# FinalSchematic1_1.net
KiCad netlist of a schematic drawn in EAGLE
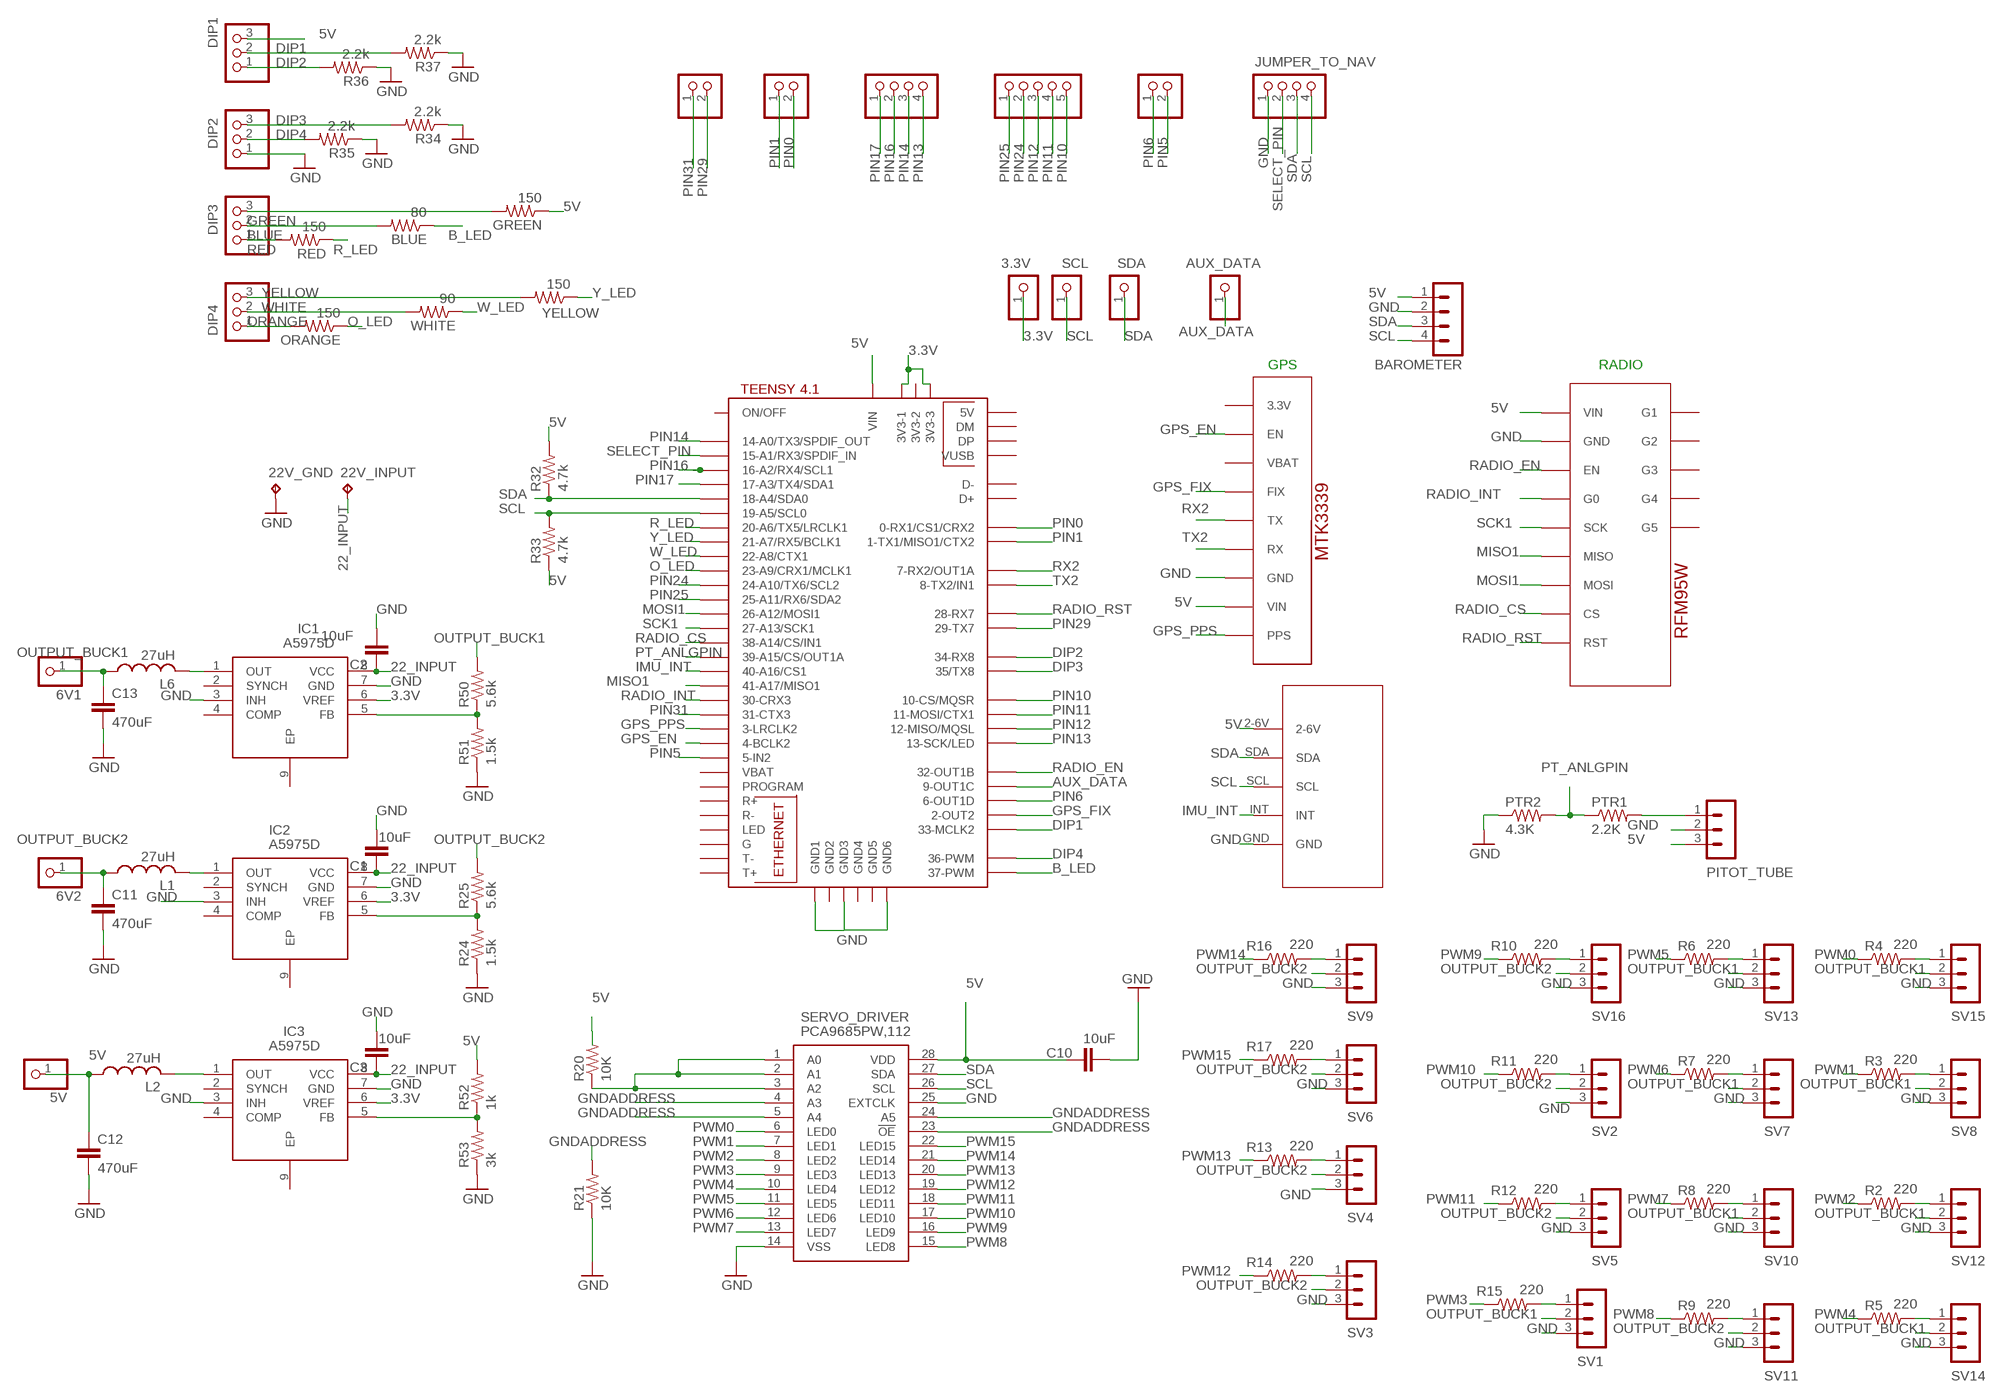
[diagram p0: schematic, sheet 1]

(export (version "E")
  (design (tool "Eeschema 10.0.6"))
  (components
    (comp (ref "1")
      (value "PINHD-1X2")
      (footprint "eagle-import:1X02")
      (libsource (lib "eagle-import") (part "PINHD-1X2"))
    )
    (comp (ref "2")
      (value "PINHD-1X2")
      (footprint "eagle-import:1X02")
      (libsource (lib "eagle-import") (part "PINHD-1X2"))
    )
    (comp (ref "3")
      (value "PINHD-1X4")
      (footprint "eagle-import:1X04")
      (libsource (lib "eagle-import") (part "PINHD-1X4"))
    )
    (comp (ref "3.3V")
      (value "PINHD-1X1")
      (footprint "eagle-import:1X01")
      (libsource (lib "eagle-import") (part "PINHD-1X1"))
    )
    (comp (ref "4")
      (value "PINHD-1X5")
      (footprint "eagle-import:1X05")
      (libsource (lib "eagle-import") (part "PINHD-1X5"))
    )
    (comp (ref "5")
      (value "PINHD-1X2")
      (footprint "eagle-import:1X02")
      (libsource (lib "eagle-import") (part "PINHD-1X2"))
    )
    (comp (ref "5V")
      (value "PINHD-1X1")
      (footprint "eagle-import:1X01")
      (libsource (lib "eagle-import") (part "PINHD-1X1"))
    )
    (comp (ref "6V1")
      (value "PINHD-1X1")
      (footprint "eagle-import:1X01")
      (libsource (lib "eagle-import") (part "PINHD-1X1"))
    )
    (comp (ref "6V2")
      (value "PINHD-1X1")
      (footprint "eagle-import:1X01")
      (libsource (lib "eagle-import") (part "PINHD-1X1"))
    )
    (comp (ref "22V_GND")
      (value "TPPAD1-17Y")
      (footprint "eagle-import:P1-17Y")
      (libsource (lib "eagle-import") (part "TPPAD1-17Y"))
    )
    (comp (ref "22V_INPUT")
      (value "TPPAD1-17Y")
      (footprint "eagle-import:P1-17Y")
      (libsource (lib "eagle-import") (part "TPPAD1-17Y"))
    )
    (comp (ref "AUX_DATA")
      (value "PINHD-1X1")
      (footprint "eagle-import:1X01")
      (libsource (lib "eagle-import") (part "PINHD-1X1"))
    )
    (comp (ref "BAROMETER")
      (value "MA04-1")
      (footprint "eagle-import:MA04-1")
      (libsource (lib "eagle-import") (part "MA04-1"))
    )
    (comp (ref "BLUE")
      (value "80")
      (footprint "eagle-import:0204_7")
      (libsource (lib "eagle-import") (part "R-US_0204/7"))
    )
    (comp (ref "C1")
      (value "10uF")
      (footprint "eagle-import:C2.5-3")
      (libsource (lib "eagle-import") (part "C2,5-3"))
    )
    (comp (ref "C2")
      (value "10uF")
      (footprint "eagle-import:C2.5-3")
      (libsource (lib "eagle-import") (part "C2,5-3"))
    )
    (comp (ref "C3")
      (value "10uF")
      (footprint "eagle-import:C2.5-3")
      (libsource (lib "eagle-import") (part "C2,5-3"))
    )
    (comp (ref "C10")
      (value "10uF")
      (footprint "eagle-import:C2.5-3")
      (libsource (lib "eagle-import") (part "C2,5-3"))
    )
    (comp (ref "C11")
      (value "470uF")
      (footprint "eagle-import:C2.5-3")
      (libsource (lib "eagle-import") (part "C2,5-3"))
    )
    (comp (ref "C12")
      (value "470uF")
      (footprint "eagle-import:C2.5-3")
      (libsource (lib "eagle-import") (part "C2,5-3"))
    )
    (comp (ref "C13")
      (value "470uF")
      (footprint "eagle-import:C2.5-3")
      (libsource (lib "eagle-import") (part "C2,5-3"))
    )
    (comp (ref "DIP1")
      (value "PINHD-1X3")
      (footprint "eagle-import:1X03")
      (libsource (lib "eagle-import") (part "PINHD-1X3"))
    )
    (comp (ref "DIP2")
      (value "PINHD-1X3")
      (footprint "eagle-import:1X03")
      (libsource (lib "eagle-import") (part "PINHD-1X3"))
    )
    (comp (ref "DIP3")
      (value "PINHD-1X3")
      (footprint "eagle-import:1X03")
      (libsource (lib "eagle-import") (part "PINHD-1X3"))
    )
    (comp (ref "DIP4")
      (value "PINHD-1X3")
      (footprint "eagle-import:1X03")
      (libsource (lib "eagle-import") (part "PINHD-1X3"))
    )
    (comp (ref "GPSMTK3339")
      (value "ADAFRUIT_MTK3339_GPS")
      (footprint "eagle-import:ADAFRUIT_MTK3339_GPS")
      (libsource (lib "eagle-import") (part "ADAFRUIT_MTK3339_GPS"))
    )
    (comp (ref "GREEN")
      (value "150")
      (footprint "eagle-import:0204_7")
      (libsource (lib "eagle-import") (part "R-US_0204/7"))
    )
    (comp (ref "IC1")
      (value "A5975D")
      (footprint "eagle-import:SOIC127P600X170-9N")
      (fields (field (name "MOUSER_PART_NUMBER") "511-A5975D"))
      (libsource (lib "eagle-import") (part "A5975D"))
    )
    (comp (ref "IC2")
      (value "A5975D")
      (footprint "eagle-import:SOIC127P600X170-9N")
      (fields (field (name "MOUSER_PART_NUMBER") "511-A5975D"))
      (libsource (lib "eagle-import") (part "A5975D"))
    )
    (comp (ref "IC3")
      (value "A5975D")
      (footprint "eagle-import:SOIC127P600X170-9N")
      (fields (field (name "MOUSER_PART_NUMBER") "511-A5975D"))
      (libsource (lib "eagle-import") (part "A5975D"))
    )
    (comp (ref "IMU")
      (value "ICM20948BREAKOUTDEVICE")
      (footprint "eagle-import:ICM20948BREAKOUT")
      (fields (field (name "SPICEPREFIX") "X"))
      (libsource (lib "eagle-import") (part "ICM20948BREAKOUTDEVICE"))
    )
    (comp (ref "JUMPER_TO_NAV")
      (value "PINHD-1X4")
      (footprint "eagle-import:1X04")
      (libsource (lib "eagle-import") (part "PINHD-1X4"))
    )
    (comp (ref "L1")
      (value "27uH")
      (footprint "eagle-import:TFI0307")
      (libsource (lib "eagle-import") (part "L-USTFI0307"))
    )
    (comp (ref "L2")
      (value "27uH")
      (footprint "eagle-import:TFI0307")
      (libsource (lib "eagle-import") (part "L-USTFI0307"))
    )
    (comp (ref "L6")
      (value "27uH")
      (footprint "eagle-import:TFI0307")
      (libsource (lib "eagle-import") (part "L-USTFI0307"))
    )
    (comp (ref "ORANGE")
      (value "150")
      (footprint "eagle-import:0204_7")
      (libsource (lib "eagle-import") (part "R-US_0204/7"))
    )
    (comp (ref "PITOT_TUBE")
      (value "MA03-1")
      (footprint "eagle-import:MA03-1")
      (libsource (lib "eagle-import") (part "MA03-1"))
    )
    (comp (ref "PTR1")
      (value "2.2K")
      (footprint "eagle-import:0204_7")
      (libsource (lib "eagle-import") (part "R-US_0204/7"))
    )
    (comp (ref "PTR2")
      (value "4.3K")
      (footprint "eagle-import:0204_7")
      (libsource (lib "eagle-import") (part "R-US_0204/7"))
    )
    (comp (ref "R2")
      (value "220")
      (footprint "eagle-import:0204_7")
      (libsource (lib "eagle-import") (part "R-US_0204/7"))
    )
    (comp (ref "R3")
      (value "220")
      (footprint "eagle-import:0204_7")
      (libsource (lib "eagle-import") (part "R-US_0204/7"))
    )
    (comp (ref "R4")
      (value "220")
      (footprint "eagle-import:0204_7")
      (libsource (lib "eagle-import") (part "R-US_0204/7"))
    )
    (comp (ref "R5")
      (value "220")
      (footprint "eagle-import:0204_7")
      (libsource (lib "eagle-import") (part "R-US_0204/7"))
    )
    (comp (ref "R6")
      (value "220")
      (footprint "eagle-import:0204_7")
      (libsource (lib "eagle-import") (part "R-US_0204/7"))
    )
    (comp (ref "R7")
      (value "220")
      (footprint "eagle-import:0204_7")
      (libsource (lib "eagle-import") (part "R-US_0204/7"))
    )
    (comp (ref "R8")
      (value "220")
      (footprint "eagle-import:0204_7")
      (libsource (lib "eagle-import") (part "R-US_0204/7"))
    )
    (comp (ref "R9")
      (value "220")
      (footprint "eagle-import:0204_7")
      (libsource (lib "eagle-import") (part "R-US_0204/7"))
    )
    (comp (ref "R10")
      (value "220")
      (footprint "eagle-import:0204_7")
      (libsource (lib "eagle-import") (part "R-US_0204/7"))
    )
    (comp (ref "R11")
      (value "220")
      (footprint "eagle-import:0204_7")
      (libsource (lib "eagle-import") (part "R-US_0204/7"))
    )
    (comp (ref "R12")
      (value "220")
      (footprint "eagle-import:0204_7")
      (libsource (lib "eagle-import") (part "R-US_0204/7"))
    )
    (comp (ref "R13")
      (value "220")
      (footprint "eagle-import:0204_7")
      (libsource (lib "eagle-import") (part "R-US_0204/7"))
    )
    (comp (ref "R14")
      (value "220")
      (footprint "eagle-import:0204_7")
      (libsource (lib "eagle-import") (part "R-US_0204/7"))
    )
    (comp (ref "R15")
      (value "220")
      (footprint "eagle-import:0204_7")
      (libsource (lib "eagle-import") (part "R-US_0204/7"))
    )
    (comp (ref "R16")
      (value "220")
      (footprint "eagle-import:0204_7")
      (libsource (lib "eagle-import") (part "R-US_0204/7"))
    )
    (comp (ref "R17")
      (value "220")
      (footprint "eagle-import:0204_7")
      (libsource (lib "eagle-import") (part "R-US_0204/7"))
    )
    (comp (ref "R20")
      (value "10K")
      (footprint "eagle-import:0204_7")
      (libsource (lib "eagle-import") (part "R-US_0204/7"))
    )
    (comp (ref "R21")
      (value "10K")
      (footprint "eagle-import:0204_7")
      (libsource (lib "eagle-import") (part "R-US_0204/7"))
    )
    (comp (ref "R24")
      (value "1.5k")
      (footprint "eagle-import:0204_7")
      (libsource (lib "eagle-import") (part "R-US_0204/7"))
    )
    (comp (ref "R25")
      (value "5.6k")
      (footprint "eagle-import:0204_7")
      (libsource (lib "eagle-import") (part "R-US_0204/7"))
    )
    (comp (ref "R32")
      (value "4.7k")
      (footprint "eagle-import:0204_7")
      (libsource (lib "eagle-import") (part "R-US_0204/7"))
    )
    (comp (ref "R33")
      (value "4.7k")
      (footprint "eagle-import:0204_7")
      (libsource (lib "eagle-import") (part "R-US_0204/7"))
    )
    (comp (ref "R34")
      (value "2.2k")
      (footprint "eagle-import:0204_7")
      (libsource (lib "eagle-import") (part "R-US_0204/7"))
    )
    (comp (ref "R35")
      (value "2.2k")
      (footprint "eagle-import:0204_7")
      (libsource (lib "eagle-import") (part "R-US_0204/7"))
    )
    (comp (ref "R36")
      (value "2.2k")
      (footprint "eagle-import:0204_7")
      (libsource (lib "eagle-import") (part "R-US_0204/7"))
    )
    (comp (ref "R37")
      (value "2.2k")
      (footprint "eagle-import:0204_7")
      (libsource (lib "eagle-import") (part "R-US_0204/7"))
    )
    (comp (ref "R50")
      (value "5.6k")
      (footprint "eagle-import:0204_7")
      (libsource (lib "eagle-import") (part "R-US_0204/7"))
    )
    (comp (ref "R51")
      (value "1.5k")
      (footprint "eagle-import:0204_7")
      (libsource (lib "eagle-import") (part "R-US_0204/7"))
    )
    (comp (ref "R52")
      (value "1k")
      (footprint "eagle-import:0204_7")
      (libsource (lib "eagle-import") (part "R-US_0204/7"))
    )
    (comp (ref "R53")
      (value "3k")
      (footprint "eagle-import:0204_7")
      (libsource (lib "eagle-import") (part "R-US_0204/7"))
    )
    (comp (ref "RADIO")
      (value "ADAFRUIT_RFM95W_LORA_RADIO")
      (footprint "eagle-import:ADAFRUIT_RFM95W_LORA_RADIO")
      (libsource (lib "eagle-import") (part "ADAFRUIT_RFM95W_LORA_RADIO"))
    )
    (comp (ref "RED")
      (value "150")
      (footprint "eagle-import:0204_7")
      (libsource (lib "eagle-import") (part "R-US_0204/7"))
    )
    (comp (ref "SCL")
      (value "PINHD-1X1")
      (footprint "eagle-import:1X01")
      (libsource (lib "eagle-import") (part "PINHD-1X1"))
    )
    (comp (ref "SDA")
      (value "PINHD-1X1")
      (footprint "eagle-import:1X01")
      (libsource (lib "eagle-import") (part "PINHD-1X1"))
    )
    (comp (ref "SERVO_DRIVER")
      (value "PCA9685PW,112")
      (footprint "eagle-import:SOP65P640X110-28N")
      (fields (field (name "MOUSER_PART_NUMBER") "771-PCA9685PW,112"))
      (libsource (lib "eagle-import") (part "PCA9685PW,112"))
    )
    (comp (ref "SV1")
      (value "MA03-1")
      (footprint "eagle-import:MA03-1")
      (libsource (lib "eagle-import") (part "MA03-1"))
    )
    (comp (ref "SV2")
      (value "MA03-1")
      (footprint "eagle-import:MA03-1")
      (libsource (lib "eagle-import") (part "MA03-1"))
    )
    (comp (ref "SV3")
      (value "MA03-1")
      (footprint "eagle-import:MA03-1")
      (libsource (lib "eagle-import") (part "MA03-1"))
    )
    (comp (ref "SV4")
      (value "MA03-1")
      (footprint "eagle-import:MA03-1")
      (libsource (lib "eagle-import") (part "MA03-1"))
    )
    (comp (ref "SV5")
      (value "MA03-1")
      (footprint "eagle-import:MA03-1")
      (libsource (lib "eagle-import") (part "MA03-1"))
    )
    (comp (ref "SV6")
      (value "MA03-1")
      (footprint "eagle-import:MA03-1")
      (libsource (lib "eagle-import") (part "MA03-1"))
    )
    (comp (ref "SV7")
      (value "MA03-1")
      (footprint "eagle-import:MA03-1")
      (libsource (lib "eagle-import") (part "MA03-1"))
    )
    (comp (ref "SV8")
      (value "MA03-1")
      (footprint "eagle-import:MA03-1")
      (libsource (lib "eagle-import") (part "MA03-1"))
    )
    (comp (ref "SV9")
      (value "MA03-1")
      (footprint "eagle-import:MA03-1")
      (libsource (lib "eagle-import") (part "MA03-1"))
    )
    (comp (ref "SV10")
      (value "MA03-1")
      (footprint "eagle-import:MA03-1")
      (libsource (lib "eagle-import") (part "MA03-1"))
    )
    (comp (ref "SV11")
      (value "MA03-1")
      (footprint "eagle-import:MA03-1")
      (libsource (lib "eagle-import") (part "MA03-1"))
    )
    (comp (ref "SV12")
      (value "MA03-1")
      (footprint "eagle-import:MA03-1")
      (libsource (lib "eagle-import") (part "MA03-1"))
    )
    (comp (ref "SV13")
      (value "MA03-1")
      (footprint "eagle-import:MA03-1")
      (libsource (lib "eagle-import") (part "MA03-1"))
    )
    (comp (ref "SV14")
      (value "MA03-1")
      (footprint "eagle-import:MA03-1")
      (libsource (lib "eagle-import") (part "MA03-1"))
    )
    (comp (ref "SV15")
      (value "MA03-1")
      (footprint "eagle-import:MA03-1")
      (libsource (lib "eagle-import") (part "MA03-1"))
    )
    (comp (ref "SV16")
      (value "MA03-1")
      (footprint "eagle-import:MA03-1")
      (libsource (lib "eagle-import") (part "MA03-1"))
    )
    (comp (ref "TEENSY4.1")
      (value "TEENSY41")
      (footprint "eagle-import:TEENSY41")
      (libsource (lib "eagle-import") (part "TEENSY41"))
    )
    (comp (ref "WHITE")
      (value "90")
      (footprint "eagle-import:0204_7")
      (libsource (lib "eagle-import") (part "R-US_0204/7"))
    )
    (comp (ref "YELLOW")
      (value "150")
      (footprint "eagle-import:0204_7")
      (libsource (lib "eagle-import") (part "R-US_0204/7"))
    )
  )
  (nets
    (net (code "1") (name "/3.3V") (class "Default")
      (node (ref "3.3V") (pin "1") (pinfunction "1_1") (pintype "passive"))
      (node (ref "IC1") (pin "6") (pinfunction "VREF_6") (pintype "bidirectional"))
      (node (ref "IC2") (pin "6") (pinfunction "VREF_6") (pintype "bidirectional"))
      (node (ref "IC3") (pin "6") (pinfunction "VREF_6") (pintype "bidirectional"))
      (node (ref "TEENSY4.1") (pin "3V3-1") (pinfunction "3V3-1_3V3-1") (pintype "bidirectional"))
      (node (ref "TEENSY4.1") (pin "3V3-3") (pinfunction "3V3-3_3V3-3") (pintype "bidirectional"))
    )
    (net (code "2") (name "/5V") (class "Default")
      (node (ref "5V") (pin "1") (pinfunction "1_1") (pintype "passive"))
      (node (ref "BAROMETER") (pin "1") (pinfunction "1_1") (pintype "passive"))
      (node (ref "C10") (pin "1") (pinfunction "1_1") (pintype "passive"))
      (node (ref "C12") (pin "1") (pinfunction "1_1") (pintype "passive"))
      (node (ref "DIP1") (pin "3") (pinfunction "3_3") (pintype "passive"))
      (node (ref "GPSMTK3339") (pin "VIN") (pinfunction "VIN_VIN") (pintype "bidirectional"))
      (node (ref "GREEN") (pin "1") (pinfunction "1_1") (pintype "passive"))
      (node (ref "IMU") (pin "2-6V") (pinfunction "2-6V_2-6V") (pintype "bidirectional"))
      (node (ref "L2") (pin "1") (pinfunction "1_1") (pintype "passive"))
      (node (ref "PITOT_TUBE") (pin "3") (pinfunction "3_3") (pintype "passive"))
      (node (ref "R20") (pin "2") (pinfunction "2_2") (pintype "passive"))
      (node (ref "R32") (pin "2") (pinfunction "2_2") (pintype "passive"))
      (node (ref "R33") (pin "1") (pinfunction "1_1") (pintype "passive"))
      (node (ref "R52") (pin "2") (pinfunction "2_2") (pintype "passive"))
      (node (ref "RADIO") (pin "1") (pinfunction "VIN_1") (pintype "bidirectional"))
      (node (ref "SERVO_DRIVER") (pin "28") (pinfunction "VDD_28") (pintype "bidirectional"))
      (node (ref "TEENSY4.1") (pin "VIN") (pinfunction "VIN_VIN") (pintype "bidirectional"))
    )
    (net (code "3") (name "/22_INPUT") (class "Default")
      (node (ref "22V_INPUT") (pin "TP") (pinfunction "TP_TP") (pintype "input"))
      (node (ref "C1") (pin "1") (pinfunction "1_1") (pintype "passive"))
      (node (ref "C2") (pin "1") (pinfunction "1_1") (pintype "passive"))
      (node (ref "C3") (pin "1") (pinfunction "1_1") (pintype "passive"))
      (node (ref "IC1") (pin "8") (pinfunction "VCC_8") (pintype "bidirectional"))
      (node (ref "IC2") (pin "8") (pinfunction "VCC_8") (pintype "bidirectional"))
      (node (ref "IC3") (pin "8") (pinfunction "VCC_8") (pintype "bidirectional"))
    )
    (net (code "4") (name "/AUX_DATA") (class "Default")
      (node (ref "AUX_DATA") (pin "1") (pinfunction "1_1") (pintype "passive"))
      (node (ref "TEENSY4.1") (pin "9-OUT1C") (pinfunction "9-OUT1C_9-OUT1C") (pintype "bidirectional"))
    )
    (net (code "5") (name "/BLUE") (class "Default")
      (node (ref "BLUE") (pin "2") (pinfunction "2_2") (pintype "passive"))
      (node (ref "DIP3") (pin "2") (pinfunction "2_2") (pintype "passive"))
    )
    (net (code "6") (name "/B_LED") (class "Default")
      (node (ref "BLUE") (pin "1") (pinfunction "1_1") (pintype "passive"))
      (node (ref "TEENSY4.1") (pin "37-PWM") (pinfunction "37-PWM_37-PWM") (pintype "bidirectional"))
    )
    (net (code "7") (name "/DIP1") (class "Default")
      (node (ref "DIP1") (pin "2") (pinfunction "2_2") (pintype "passive"))
      (node (ref "R37") (pin "2") (pinfunction "2_2") (pintype "passive"))
      (node (ref "TEENSY4.1") (pin "33-MCLK2") (pinfunction "33-MCLK2_33-MCLK2") (pintype "bidirectional"))
    )
    (net (code "8") (name "/DIP2") (class "Default")
      (node (ref "DIP1") (pin "1") (pinfunction "1_1") (pintype "passive"))
      (node (ref "R36") (pin "2") (pinfunction "2_2") (pintype "passive"))
      (node (ref "TEENSY4.1") (pin "34-RX8") (pinfunction "34-RX8_34-RX8") (pintype "bidirectional"))
    )
    (net (code "9") (name "/DIP3") (class "Default")
      (node (ref "DIP2") (pin "3") (pinfunction "3_3") (pintype "passive"))
      (node (ref "R34") (pin "2") (pinfunction "2_2") (pintype "passive"))
      (node (ref "TEENSY4.1") (pin "35-TX8") (pinfunction "35/TX8_35-TX8") (pintype "bidirectional"))
    )
    (net (code "10") (name "/DIP4") (class "Default")
      (node (ref "DIP2") (pin "2") (pinfunction "2_2") (pintype "passive"))
      (node (ref "R35") (pin "2") (pinfunction "2_2") (pintype "passive"))
      (node (ref "TEENSY4.1") (pin "36-PWM") (pinfunction "36-PWM_36-PWM") (pintype "bidirectional"))
    )
    (net (code "11") (name "/GNDADDRESS") (class "Default")
      (node (ref "R21") (pin "2") (pinfunction "2_2") (pintype "passive"))
      (node (ref "SERVO_DRIVER") (pin "23") (pinfunction "~{OE}_23") (pintype "bidirectional"))
      (node (ref "SERVO_DRIVER") (pin "24") (pinfunction "A5_24") (pintype "bidirectional"))
      (node (ref "SERVO_DRIVER") (pin "4") (pinfunction "A3_4") (pintype "bidirectional"))
      (node (ref "SERVO_DRIVER") (pin "5") (pinfunction "A4_5") (pintype "bidirectional"))
    )
    (net (code "12") (name "/GPS_EN") (class "Default")
      (node (ref "GPSMTK3339") (pin "EN") (pinfunction "EN_EN") (pintype "bidirectional"))
      (node (ref "TEENSY4.1") (pin "4-BCLK2") (pinfunction "4-BCLK2_4-BCLK2") (pintype "bidirectional"))
    )
    (net (code "13") (name "/GPS_FIX") (class "Default")
      (node (ref "GPSMTK3339") (pin "FIX") (pinfunction "FIX_FIX") (pintype "bidirectional"))
      (node (ref "TEENSY4.1") (pin "2-OUT2") (pinfunction "2-OUT2_2-OUT2") (pintype "bidirectional"))
    )
    (net (code "14") (name "/GPS_PPS") (class "Default")
      (node (ref "GPSMTK3339") (pin "PPS") (pinfunction "PPS_PPS") (pintype "bidirectional"))
      (node (ref "TEENSY4.1") (pin "3-LRCLK2") (pinfunction "3-LRCLK2_3-LRCLK2") (pintype "bidirectional"))
    )
    (net (code "15") (name "/GREEN") (class "Default")
      (node (ref "DIP3") (pin "3") (pinfunction "3_3") (pintype "passive"))
      (node (ref "GREEN") (pin "2") (pinfunction "2_2") (pintype "passive"))
    )
    (net (code "16") (name "/IMU_INT") (class "Default")
      (node (ref "IMU") (pin "INT") (pinfunction "INT_INT") (pintype "bidirectional"))
      (node (ref "TEENSY4.1") (pin "40-A16/CS1") (pinfunction "40-A16/CS1_40-A16/CS1") (pintype "bidirectional"))
    )
    (net (code "17") (name "/MISO1") (class "Default")
      (node (ref "RADIO") (pin "6") (pinfunction "MISO_6") (pintype "bidirectional"))
      (node (ref "TEENSY4.1") (pin "41-A17/MISO1") (pinfunction "41-A17/MISO1_41-A17/MISO1") (pintype "bidirectional"))
    )
    (net (code "18") (name "/MOSI1") (class "Default")
      (node (ref "RADIO") (pin "7") (pinfunction "MOSI_7") (pintype "bidirectional"))
      (node (ref "TEENSY4.1") (pin "26-A12/MOSI1") (pinfunction "26-A12/MOSI1_26-A12/MOSI1") (pintype "bidirectional"))
    )
    (net (code "19") (name "/ORANGE") (class "Default")
      (node (ref "DIP4") (pin "1") (pinfunction "1_1") (pintype "passive"))
      (node (ref "ORANGE") (pin "2") (pinfunction "2_2") (pintype "passive"))
    )
    (net (code "20") (name "/OUTPUT_BUCK1") (class "Default")
      (node (ref "6V1") (pin "1") (pinfunction "1_1") (pintype "passive"))
      (node (ref "C13") (pin "1") (pinfunction "1_1") (pintype "passive"))
      (node (ref "L6") (pin "1") (pinfunction "1_1") (pintype "passive"))
      (node (ref "R50") (pin "2") (pinfunction "2_2") (pintype "passive"))
      (node (ref "SV1") (pin "2") (pinfunction "2_2") (pintype "passive"))
      (node (ref "SV10") (pin "2") (pinfunction "2_2") (pintype "passive"))
      (node (ref "SV12") (pin "2") (pinfunction "2_2") (pintype "passive"))
      (node (ref "SV13") (pin "2") (pinfunction "2_2") (pintype "passive"))
      (node (ref "SV14") (pin "2") (pinfunction "2_2") (pintype "passive"))
      (node (ref "SV15") (pin "2") (pinfunction "2_2") (pintype "passive"))
      (node (ref "SV7") (pin "2") (pinfunction "2_2") (pintype "passive"))
      (node (ref "SV8") (pin "2") (pinfunction "2_2") (pintype "passive"))
    )
    (net (code "21") (name "/OUTPUT_BUCK2") (class "Default")
      (node (ref "6V2") (pin "1") (pinfunction "1_1") (pintype "passive"))
      (node (ref "C11") (pin "1") (pinfunction "1_1") (pintype "passive"))
      (node (ref "L1") (pin "1") (pinfunction "1_1") (pintype "passive"))
      (node (ref "R25") (pin "2") (pinfunction "2_2") (pintype "passive"))
      (node (ref "SV11") (pin "2") (pinfunction "2_2") (pintype "passive"))
      (node (ref "SV16") (pin "2") (pinfunction "2_2") (pintype "passive"))
      (node (ref "SV2") (pin "2") (pinfunction "2_2") (pintype "passive"))
      (node (ref "SV3") (pin "2") (pinfunction "2_2") (pintype "passive"))
      (node (ref "SV4") (pin "2") (pinfunction "2_2") (pintype "passive"))
      (node (ref "SV5") (pin "2") (pinfunction "2_2") (pintype "passive"))
      (node (ref "SV6") (pin "2") (pinfunction "2_2") (pintype "passive"))
      (node (ref "SV9") (pin "2") (pinfunction "2_2") (pintype "passive"))
    )
    (net (code "22") (name "/O_LED") (class "Default")
      (node (ref "ORANGE") (pin "1") (pinfunction "1_1") (pintype "passive"))
      (node (ref "TEENSY4.1") (pin "23-A9/CRX1/MCLK1") (pinfunction "23-A9/CRX1/MCLK1_23-A9/CRX1/MCLK1") (pintype "bidirectional"))
    )
    (net (code "23") (name "/PIN0") (class "Default")
      (node (ref "2") (pin "2") (pinfunction "2_2") (pintype "passive"))
      (node (ref "TEENSY4.1") (pin "0-RX1/CS1/CRX2") (pinfunction "0-RX1/CS1/CRX2_0-RX1/CS1/CRX2") (pintype "bidirectional"))
    )
    (net (code "24") (name "/PIN1") (class "Default")
      (node (ref "2") (pin "1") (pinfunction "1_1") (pintype "passive"))
      (node (ref "TEENSY4.1") (pin "1-TX1/MISO1/CTX2") (pinfunction "1-TX1/MISO1/CTX2_1-TX1/MISO1/CTX2") (pintype "bidirectional"))
    )
    (net (code "25") (name "/PIN5") (class "Default")
      (node (ref "5") (pin "2") (pinfunction "2_2") (pintype "passive"))
      (node (ref "TEENSY4.1") (pin "5-IN2") (pinfunction "5-IN2_5-IN2") (pintype "bidirectional"))
    )
    (net (code "26") (name "/PIN6") (class "Default")
      (node (ref "5") (pin "1") (pinfunction "1_1") (pintype "passive"))
      (node (ref "TEENSY4.1") (pin "6-OUT1D") (pinfunction "6-OUT1D_6-OUT1D") (pintype "bidirectional"))
    )
    (net (code "27") (name "/PIN10") (class "Default")
      (node (ref "4") (pin "5") (pinfunction "5_5") (pintype "passive"))
      (node (ref "TEENSY4.1") (pin "10-CS\\MQSR") (pinfunction "10-CS/MQSR_10-CS\\MQSR") (pintype "bidirectional"))
    )
    (net (code "28") (name "/PIN11") (class "Default")
      (node (ref "4") (pin "4") (pinfunction "4_4") (pintype "passive"))
      (node (ref "TEENSY4.1") (pin "11-MOSI/CTX1") (pinfunction "11-MOSI/CTX1_11-MOSI/CTX1") (pintype "bidirectional"))
    )
    (net (code "29") (name "/PIN12") (class "Default")
      (node (ref "4") (pin "3") (pinfunction "3_3") (pintype "passive"))
      (node (ref "TEENSY4.1") (pin "12-MISO/MQSL") (pinfunction "12-MISO/MQSL_12-MISO/MQSL") (pintype "bidirectional"))
    )
    (net (code "30") (name "/PIN13") (class "Default")
      (node (ref "3") (pin "4") (pinfunction "4_4") (pintype "passive"))
      (node (ref "TEENSY4.1") (pin "13-SCK/LED") (pinfunction "13-SCK/LED_13-SCK/LED") (pintype "bidirectional"))
    )
    (net (code "31") (name "/PIN14") (class "Default")
      (node (ref "3") (pin "3") (pinfunction "3_3") (pintype "passive"))
      (node (ref "TEENSY4.1") (pin "14-A0/TX3/SPDIF_OUT") (pinfunction "14-A0/TX3/SPDIF_OUT_14-A0/TX3/SPDIF_OUT") (pintype "bidirectional"))
    )
    (net (code "32") (name "/PIN16") (class "Default")
      (node (ref "3") (pin "2") (pinfunction "2_2") (pintype "passive"))
      (node (ref "TEENSY4.1") (pin "16-A2/RX4/SCL1") (pinfunction "16-A2/RX4/SCL1_16-A2/RX4/SCL1") (pintype "bidirectional"))
    )
    (net (code "33") (name "/PIN17") (class "Default")
      (node (ref "3") (pin "1") (pinfunction "1_1") (pintype "passive"))
      (node (ref "TEENSY4.1") (pin "17-A3/TX4/SDA1") (pinfunction "17-A3/TX4/SDA1_17-A3/TX4/SDA1") (pintype "bidirectional"))
    )
    (net (code "34") (name "/PIN24") (class "Default")
      (node (ref "4") (pin "2") (pinfunction "2_2") (pintype "passive"))
      (node (ref "TEENSY4.1") (pin "24-A10/TX6/SCL2") (pinfunction "24-A10/TX6/SCL2_24-A10/TX6/SCL2") (pintype "bidirectional"))
    )
    (net (code "35") (name "/PIN25") (class "Default")
      (node (ref "4") (pin "1") (pinfunction "1_1") (pintype "passive"))
      (node (ref "TEENSY4.1") (pin "25-A11/RX6/SDA2") (pinfunction "25-A11/RX6/SDA2_25-A11/RX6/SDA2") (pintype "bidirectional"))
    )
    (net (code "36") (name "/PIN29") (class "Default")
      (node (ref "1") (pin "2") (pinfunction "2_2") (pintype "passive"))
      (node (ref "TEENSY4.1") (pin "29-TX7") (pinfunction "29-TX7_29-TX7") (pintype "bidirectional"))
    )
    (net (code "37") (name "/PIN31") (class "Default")
      (node (ref "1") (pin "1") (pinfunction "1_1") (pintype "passive"))
      (node (ref "TEENSY4.1") (pin "31-CTX3") (pinfunction "31-CTX3_31-CTX3") (pintype "bidirectional"))
    )
    (net (code "38") (name "/PT_ANLGPIN") (class "Default")
      (node (ref "PTR1") (pin "1") (pinfunction "1_1") (pintype "passive"))
      (node (ref "PTR2") (pin "2") (pinfunction "2_2") (pintype "passive"))
      (node (ref "TEENSY4.1") (pin "39-A15/CS/OUT1A") (pinfunction "39-A15/CS/OUT1A_39-A15/CS/OUT1A") (pintype "bidirectional"))
    )
    (net (code "39") (name "/PWM0") (class "Default")
      (node (ref "R4") (pin "1") (pinfunction "1_1") (pintype "passive"))
      (node (ref "SERVO_DRIVER") (pin "6") (pinfunction "LED0_6") (pintype "bidirectional"))
    )
    (net (code "40") (name "/PWM1") (class "Default")
      (node (ref "R3") (pin "1") (pinfunction "1_1") (pintype "passive"))
      (node (ref "SERVO_DRIVER") (pin "7") (pinfunction "LED1_7") (pintype "bidirectional"))
    )
    (net (code "41") (name "/PWM2") (class "Default")
      (node (ref "R2") (pin "1") (pinfunction "1_1") (pintype "passive"))
      (node (ref "SERVO_DRIVER") (pin "8") (pinfunction "LED2_8") (pintype "bidirectional"))
    )
    (net (code "42") (name "/PWM3") (class "Default")
      (node (ref "R15") (pin "1") (pinfunction "1_1") (pintype "passive"))
      (node (ref "SERVO_DRIVER") (pin "9") (pinfunction "LED3_9") (pintype "bidirectional"))
    )
    (net (code "43") (name "/PWM4") (class "Default")
      (node (ref "R5") (pin "1") (pinfunction "1_1") (pintype "passive"))
      (node (ref "SERVO_DRIVER") (pin "10") (pinfunction "LED4_10") (pintype "bidirectional"))
    )
    (net (code "44") (name "/PWM5") (class "Default")
      (node (ref "R6") (pin "1") (pinfunction "1_1") (pintype "passive"))
      (node (ref "SERVO_DRIVER") (pin "11") (pinfunction "LED5_11") (pintype "bidirectional"))
    )
    (net (code "45") (name "/PWM6") (class "Default")
      (node (ref "R7") (pin "1") (pinfunction "1_1") (pintype "passive"))
      (node (ref "SERVO_DRIVER") (pin "12") (pinfunction "LED6_12") (pintype "bidirectional"))
    )
    (net (code "46") (name "/PWM7") (class "Default")
      (node (ref "R8") (pin "1") (pinfunction "1_1") (pintype "passive"))
      (node (ref "SERVO_DRIVER") (pin "13") (pinfunction "LED7_13") (pintype "bidirectional"))
    )
    (net (code "47") (name "/PWM8") (class "Default")
      (node (ref "R9") (pin "1") (pinfunction "1_1") (pintype "passive"))
      (node (ref "SERVO_DRIVER") (pin "15") (pinfunction "LED8_15") (pintype "bidirectional"))
    )
    (net (code "48") (name "/PWM9") (class "Default")
      (node (ref "R10") (pin "1") (pinfunction "1_1") (pintype "passive"))
      (node (ref "SERVO_DRIVER") (pin "16") (pinfunction "LED9_16") (pintype "bidirectional"))
    )
    (net (code "49") (name "/PWM10") (class "Default")
      (node (ref "R11") (pin "1") (pinfunction "1_1") (pintype "passive"))
      (node (ref "SERVO_DRIVER") (pin "17") (pinfunction "LED10_17") (pintype "bidirectional"))
    )
    (net (code "50") (name "/PWM11") (class "Default")
      (node (ref "R12") (pin "1") (pinfunction "1_1") (pintype "passive"))
      (node (ref "SERVO_DRIVER") (pin "18") (pinfunction "LED11_18") (pintype "bidirectional"))
    )
    (net (code "51") (name "/PWM12") (class "Default")
      (node (ref "R14") (pin "1") (pinfunction "1_1") (pintype "passive"))
      (node (ref "SERVO_DRIVER") (pin "19") (pinfunction "LED12_19") (pintype "bidirectional"))
    )
    (net (code "52") (name "/PWM13") (class "Default")
      (node (ref "R13") (pin "1") (pinfunction "1_1") (pintype "passive"))
      (node (ref "SERVO_DRIVER") (pin "20") (pinfunction "LED13_20") (pintype "bidirectional"))
    )
    (net (code "53") (name "/PWM14") (class "Default")
      (node (ref "R16") (pin "1") (pinfunction "1_1") (pintype "passive"))
      (node (ref "SERVO_DRIVER") (pin "21") (pinfunction "LED14_21") (pintype "bidirectional"))
    )
    (net (code "54") (name "/PWM15") (class "Default")
      (node (ref "R17") (pin "1") (pinfunction "1_1") (pintype "passive"))
      (node (ref "SERVO_DRIVER") (pin "22") (pinfunction "LED15_22") (pintype "bidirectional"))
    )
    (net (code "55") (name "/RADIO_CS") (class "Default")
      (node (ref "RADIO") (pin "8") (pinfunction "CS_8") (pintype "bidirectional"))
      (node (ref "TEENSY4.1") (pin "38-A14/CS/IN1") (pinfunction "38-A14/CS/IN1_38-A14/CS/IN1") (pintype "bidirectional"))
    )
    (net (code "56") (name "/RADIO_EN") (class "Default")
      (node (ref "RADIO") (pin "3") (pinfunction "EN_3") (pintype "bidirectional"))
      (node (ref "TEENSY4.1") (pin "32-OUT1B") (pinfunction "32-OUT1B_32-OUT1B") (pintype "bidirectional"))
    )
    (net (code "57") (name "/RADIO_INT") (class "Default")
      (node (ref "RADIO") (pin "4") (pinfunction "G0_4") (pintype "bidirectional"))
      (node (ref "TEENSY4.1") (pin "30-CRX3") (pinfunction "30-CRX3_30-CRX3") (pintype "bidirectional"))
    )
    (net (code "58") (name "/RADIO_RST") (class "Default")
      (node (ref "RADIO") (pin "9") (pinfunction "RST_9") (pintype "bidirectional"))
      (node (ref "TEENSY4.1") (pin "28-RX7") (pinfunction "28-RX7_28-RX7") (pintype "bidirectional"))
    )
    (net (code "59") (name "/RED") (class "Default")
      (node (ref "DIP3") (pin "1") (pinfunction "1_1") (pintype "passive"))
      (node (ref "RED") (pin "2") (pinfunction "2_2") (pintype "passive"))
    )
    (net (code "60") (name "/RX2") (class "Default")
      (node (ref "GPSMTK3339") (pin "TX") (pinfunction "TX_TX") (pintype "bidirectional"))
      (node (ref "TEENSY4.1") (pin "7-RX2/OUT1A") (pinfunction "7-RX2/OUT1A_7-RX2/OUT1A") (pintype "bidirectional"))
    )
    (net (code "61") (name "/R_LED") (class "Default")
      (node (ref "RED") (pin "1") (pinfunction "1_1") (pintype "passive"))
      (node (ref "TEENSY4.1") (pin "20-A6/TX5/LRCLK1") (pinfunction "20-A6/TX5/LRCLK1_20-A6/TX5/LRCLK1") (pintype "bidirectional"))
    )
    (net (code "62") (name "/SCK1") (class "Default")
      (node (ref "RADIO") (pin "5") (pinfunction "SCK_5") (pintype "bidirectional"))
      (node (ref "TEENSY4.1") (pin "27-A13/SCK1") (pinfunction "27-A13/SCK1_27-A13/SCK1") (pintype "bidirectional"))
    )
    (net (code "63") (name "/SCL") (class "Default")
      (node (ref "BAROMETER") (pin "4") (pinfunction "4_4") (pintype "passive"))
      (node (ref "IMU") (pin "SCL") (pinfunction "SCL_SCL") (pintype "bidirectional"))
      (node (ref "JUMPER_TO_NAV") (pin "4") (pinfunction "4_4") (pintype "passive"))
      (node (ref "R33") (pin "2") (pinfunction "2_2") (pintype "passive"))
      (node (ref "SCL") (pin "1") (pinfunction "1_1") (pintype "passive"))
      (node (ref "SERVO_DRIVER") (pin "26") (pinfunction "SCL_26") (pintype "bidirectional"))
      (node (ref "TEENSY4.1") (pin "19-A5/SCL0") (pinfunction "19-A5/SCL0_19-A5/SCL0") (pintype "bidirectional"))
    )
    (net (code "64") (name "/SDA") (class "Default")
      (node (ref "BAROMETER") (pin "3") (pinfunction "3_3") (pintype "passive"))
      (node (ref "IMU") (pin "SDA") (pinfunction "SDA_SDA") (pintype "bidirectional"))
      (node (ref "JUMPER_TO_NAV") (pin "3") (pinfunction "3_3") (pintype "passive"))
      (node (ref "R32") (pin "1") (pinfunction "1_1") (pintype "passive"))
      (node (ref "SDA") (pin "1") (pinfunction "1_1") (pintype "passive"))
      (node (ref "SERVO_DRIVER") (pin "27") (pinfunction "SDA_27") (pintype "bidirectional"))
      (node (ref "TEENSY4.1") (pin "18-A4/SDA0") (pinfunction "18-A4/SDA0_18-A4/SDA0") (pintype "bidirectional"))
    )
    (net (code "65") (name "/SELECT_PIN") (class "Default")
      (node (ref "JUMPER_TO_NAV") (pin "2") (pinfunction "2_2") (pintype "passive"))
      (node (ref "TEENSY4.1") (pin "15-A1/RX3/SPDIF_IN") (pinfunction "15-A1/RX3/SPDIF_IN_15-A1/RX3/SPDIF_IN") (pintype "bidirectional"))
    )
    (net (code "66") (name "/TX2") (class "Default")
      (node (ref "GPSMTK3339") (pin "RX") (pinfunction "RX_RX") (pintype "bidirectional"))
      (node (ref "TEENSY4.1") (pin "8-TX2/IN1") (pinfunction "8-TX2/IN1_8-TX2/IN1") (pintype "bidirectional"))
    )
    (net (code "67") (name "/WHITE") (class "Default")
      (node (ref "DIP4") (pin "2") (pinfunction "2_2") (pintype "passive"))
      (node (ref "WHITE") (pin "2") (pinfunction "2_2") (pintype "passive"))
    )
    (net (code "68") (name "/W_LED") (class "Default")
      (node (ref "TEENSY4.1") (pin "22-A8/CTX1") (pinfunction "22-A8/CTX1_22-A8/CTX1") (pintype "bidirectional"))
      (node (ref "WHITE") (pin "1") (pinfunction "1_1") (pintype "passive"))
    )
    (net (code "69") (name "/YELLOW") (class "Default")
      (node (ref "DIP4") (pin "3") (pinfunction "3_3") (pintype "passive"))
      (node (ref "YELLOW") (pin "2") (pinfunction "2_2") (pintype "passive"))
    )
    (net (code "70") (name "/Y_LED") (class "Default")
      (node (ref "TEENSY4.1") (pin "21-A7/RX5/BCLK1") (pinfunction "21-A7/RX5/BCLK1_21-A7/RX5/BCLK1") (pintype "bidirectional"))
      (node (ref "YELLOW") (pin "1") (pinfunction "1_1") (pintype "passive"))
    )
    (net (code "71") (name "GND") (class "Default")
      (node (ref "22V_GND") (pin "TP") (pinfunction "TP_TP") (pintype "input"))
      (node (ref "BAROMETER") (pin "2") (pinfunction "2_2") (pintype "passive"))
      (node (ref "C1") (pin "2") (pinfunction "2_2") (pintype "passive"))
      (node (ref "C10") (pin "2") (pinfunction "2_2") (pintype "passive"))
      (node (ref "C11") (pin "2") (pinfunction "2_2") (pintype "passive"))
      (node (ref "C12") (pin "2") (pinfunction "2_2") (pintype "passive"))
      (node (ref "C13") (pin "2") (pinfunction "2_2") (pintype "passive"))
      (node (ref "C2") (pin "2") (pinfunction "2_2") (pintype "passive"))
      (node (ref "C3") (pin "2") (pinfunction "2_2") (pintype "passive"))
      (node (ref "DIP2") (pin "1") (pinfunction "1_1") (pintype "passive"))
      (node (ref "GPSMTK3339") (pin "GND") (pinfunction "GND_GND") (pintype "bidirectional"))
      (node (ref "IC1") (pin "3") (pinfunction "INH_3") (pintype "bidirectional"))
      (node (ref "IC1") (pin "7") (pinfunction "GND_7") (pintype "bidirectional"))
      (node (ref "IC2") (pin "3") (pinfunction "INH_3") (pintype "bidirectional"))
      (node (ref "IC2") (pin "7") (pinfunction "GND_7") (pintype "bidirectional"))
      (node (ref "IC3") (pin "3") (pinfunction "INH_3") (pintype "bidirectional"))
      (node (ref "IC3") (pin "7") (pinfunction "GND_7") (pintype "bidirectional"))
      (node (ref "IMU") (pin "GND") (pinfunction "GND_GND") (pintype "bidirectional"))
      (node (ref "JUMPER_TO_NAV") (pin "1") (pinfunction "1_1") (pintype "passive"))
      (node (ref "PITOT_TUBE") (pin "2") (pinfunction "2_2") (pintype "passive"))
      (node (ref "PTR2") (pin "1") (pinfunction "1_1") (pintype "passive"))
      (node (ref "R21") (pin "1") (pinfunction "1_1") (pintype "passive"))
      (node (ref "R24") (pin "1") (pinfunction "1_1") (pintype "passive"))
      (node (ref "R34") (pin "1") (pinfunction "1_1") (pintype "passive"))
      (node (ref "R35") (pin "1") (pinfunction "1_1") (pintype "passive"))
      (node (ref "R36") (pin "1") (pinfunction "1_1") (pintype "passive"))
      (node (ref "R37") (pin "1") (pinfunction "1_1") (pintype "passive"))
      (node (ref "R51") (pin "1") (pinfunction "1_1") (pintype "passive"))
      (node (ref "R53") (pin "1") (pinfunction "1_1") (pintype "passive"))
      (node (ref "RADIO") (pin "2") (pinfunction "GND_2") (pintype "bidirectional"))
      (node (ref "SERVO_DRIVER") (pin "14") (pinfunction "VSS_14") (pintype "bidirectional"))
      (node (ref "SERVO_DRIVER") (pin "25") (pinfunction "EXTCLK_25") (pintype "bidirectional"))
      (node (ref "SV1") (pin "3") (pinfunction "3_3") (pintype "passive"))
      (node (ref "SV10") (pin "3") (pinfunction "3_3") (pintype "passive"))
      (node (ref "SV11") (pin "3") (pinfunction "3_3") (pintype "passive"))
      (node (ref "SV12") (pin "3") (pinfunction "3_3") (pintype "passive"))
      (node (ref "SV13") (pin "3") (pinfunction "3_3") (pintype "passive"))
      (node (ref "SV14") (pin "3") (pinfunction "3_3") (pintype "passive"))
      (node (ref "SV15") (pin "3") (pinfunction "3_3") (pintype "passive"))
      (node (ref "SV16") (pin "3") (pinfunction "3_3") (pintype "passive"))
      (node (ref "SV2") (pin "3") (pinfunction "3_3") (pintype "passive"))
      (node (ref "SV3") (pin "3") (pinfunction "3_3") (pintype "passive"))
      (node (ref "SV4") (pin "3") (pinfunction "3_3") (pintype "passive"))
      (node (ref "SV5") (pin "3") (pinfunction "3_3") (pintype "passive"))
      (node (ref "SV6") (pin "3") (pinfunction "3_3") (pintype "passive"))
      (node (ref "SV7") (pin "3") (pinfunction "3_3") (pintype "passive"))
      (node (ref "SV8") (pin "3") (pinfunction "3_3") (pintype "passive"))
      (node (ref "SV9") (pin "3") (pinfunction "3_3") (pintype "passive"))
      (node (ref "TEENSY4.1") (pin "GND1") (pinfunction "GND1_GND1") (pintype "bidirectional"))
      (node (ref "TEENSY4.1") (pin "GND3") (pinfunction "GND3_GND3") (pintype "bidirectional"))
      (node (ref "TEENSY4.1") (pin "GND6") (pinfunction "GND6_GND6") (pintype "bidirectional"))
    )
    (net (code "72") (name "Net-(IC1-FB)") (class "Default")
      (node (ref "IC1") (pin "5") (pinfunction "FB_5") (pintype "bidirectional"))
      (node (ref "R50") (pin "1") (pinfunction "1_1") (pintype "passive"))
      (node (ref "R51") (pin "2") (pinfunction "2_2") (pintype "passive"))
    )
    (net (code "73") (name "Net-(IC1-OUT)") (class "Default")
      (node (ref "IC1") (pin "1") (pinfunction "OUT_1") (pintype "bidirectional"))
      (node (ref "L6") (pin "2") (pinfunction "2_2") (pintype "passive"))
    )
    (net (code "74") (name "Net-(IC2-FB)") (class "Default")
      (node (ref "IC2") (pin "5") (pinfunction "FB_5") (pintype "bidirectional"))
      (node (ref "R24") (pin "2") (pinfunction "2_2") (pintype "passive"))
      (node (ref "R25") (pin "1") (pinfunction "1_1") (pintype "passive"))
    )
    (net (code "75") (name "Net-(IC2-OUT)") (class "Default")
      (node (ref "IC2") (pin "1") (pinfunction "OUT_1") (pintype "bidirectional"))
      (node (ref "L1") (pin "2") (pinfunction "2_2") (pintype "passive"))
    )
    (net (code "76") (name "Net-(IC3-FB)") (class "Default")
      (node (ref "IC3") (pin "5") (pinfunction "FB_5") (pintype "bidirectional"))
      (node (ref "R52") (pin "1") (pinfunction "1_1") (pintype "passive"))
      (node (ref "R53") (pin "2") (pinfunction "2_2") (pintype "passive"))
    )
    (net (code "77") (name "Net-(IC3-OUT)") (class "Default")
      (node (ref "IC3") (pin "1") (pinfunction "OUT_1") (pintype "bidirectional"))
      (node (ref "L2") (pin "2") (pinfunction "2_2") (pintype "passive"))
    )
    (net (code "78") (name "Net-(PITOT_TUBE-Pad1)") (class "Default")
      (node (ref "PITOT_TUBE") (pin "1") (pinfunction "1_1") (pintype "passive"))
      (node (ref "PTR1") (pin "2") (pinfunction "2_2") (pintype "passive"))
    )
    (net (code "79") (name "Net-(R2-Pad2)") (class "Default")
      (node (ref "R2") (pin "2") (pinfunction "2_2") (pintype "passive"))
      (node (ref "SV12") (pin "1") (pinfunction "1_1") (pintype "passive"))
    )
    (net (code "80") (name "Net-(R3-Pad2)") (class "Default")
      (node (ref "R3") (pin "2") (pinfunction "2_2") (pintype "passive"))
      (node (ref "SV8") (pin "1") (pinfunction "1_1") (pintype "passive"))
    )
    (net (code "81") (name "Net-(R4-Pad2)") (class "Default")
      (node (ref "R4") (pin "2") (pinfunction "2_2") (pintype "passive"))
      (node (ref "SV15") (pin "1") (pinfunction "1_1") (pintype "passive"))
    )
    (net (code "82") (name "Net-(R5-Pad2)") (class "Default")
      (node (ref "R5") (pin "2") (pinfunction "2_2") (pintype "passive"))
      (node (ref "SV14") (pin "1") (pinfunction "1_1") (pintype "passive"))
    )
    (net (code "83") (name "Net-(R6-Pad2)") (class "Default")
      (node (ref "R6") (pin "2") (pinfunction "2_2") (pintype "passive"))
      (node (ref "SV13") (pin "1") (pinfunction "1_1") (pintype "passive"))
    )
    (net (code "84") (name "Net-(R7-Pad2)") (class "Default")
      (node (ref "R7") (pin "2") (pinfunction "2_2") (pintype "passive"))
      (node (ref "SV7") (pin "1") (pinfunction "1_1") (pintype "passive"))
    )
    (net (code "85") (name "Net-(R8-Pad2)") (class "Default")
      (node (ref "R8") (pin "2") (pinfunction "2_2") (pintype "passive"))
      (node (ref "SV10") (pin "1") (pinfunction "1_1") (pintype "passive"))
    )
    (net (code "86") (name "Net-(R9-Pad2)") (class "Default")
      (node (ref "R9") (pin "2") (pinfunction "2_2") (pintype "passive"))
      (node (ref "SV11") (pin "1") (pinfunction "1_1") (pintype "passive"))
    )
    (net (code "87") (name "Net-(R10-Pad2)") (class "Default")
      (node (ref "R10") (pin "2") (pinfunction "2_2") (pintype "passive"))
      (node (ref "SV16") (pin "1") (pinfunction "1_1") (pintype "passive"))
    )
    (net (code "88") (name "Net-(R11-Pad2)") (class "Default")
      (node (ref "R11") (pin "2") (pinfunction "2_2") (pintype "passive"))
      (node (ref "SV2") (pin "1") (pinfunction "1_1") (pintype "passive"))
    )
    (net (code "89") (name "Net-(R12-Pad2)") (class "Default")
      (node (ref "R12") (pin "2") (pinfunction "2_2") (pintype "passive"))
      (node (ref "SV5") (pin "1") (pinfunction "1_1") (pintype "passive"))
    )
    (net (code "90") (name "Net-(R13-Pad2)") (class "Default")
      (node (ref "R13") (pin "2") (pinfunction "2_2") (pintype "passive"))
      (node (ref "SV4") (pin "1") (pinfunction "1_1") (pintype "passive"))
    )
    (net (code "91") (name "Net-(R14-Pad2)") (class "Default")
      (node (ref "R14") (pin "2") (pinfunction "2_2") (pintype "passive"))
      (node (ref "SV3") (pin "1") (pinfunction "1_1") (pintype "passive"))
    )
    (net (code "92") (name "Net-(R15-Pad2)") (class "Default")
      (node (ref "R15") (pin "2") (pinfunction "2_2") (pintype "passive"))
      (node (ref "SV1") (pin "1") (pinfunction "1_1") (pintype "passive"))
    )
    (net (code "93") (name "Net-(R16-Pad2)") (class "Default")
      (node (ref "R16") (pin "2") (pinfunction "2_2") (pintype "passive"))
      (node (ref "SV9") (pin "1") (pinfunction "1_1") (pintype "passive"))
    )
    (net (code "94") (name "Net-(R17-Pad2)") (class "Default")
      (node (ref "R17") (pin "2") (pinfunction "2_2") (pintype "passive"))
      (node (ref "SV6") (pin "1") (pinfunction "1_1") (pintype "passive"))
    )
    (net (code "95") (name "Net-(SERVO_DRIVER-A0)") (class "Default")
      (node (ref "R20") (pin "1") (pinfunction "1_1") (pintype "passive"))
      (node (ref "SERVO_DRIVER") (pin "1") (pinfunction "A0_1") (pintype "bidirectional"))
      (node (ref "SERVO_DRIVER") (pin "2") (pinfunction "A1_2") (pintype "bidirectional"))
      (node (ref "SERVO_DRIVER") (pin "3") (pinfunction "A2_3") (pintype "bidirectional"))
    )
    (net (code "96") (name "unconnected-(GPSMTK3339-Pad3.3V)") (class "Default")
      (node (ref "GPSMTK3339") (pin "3.3V") (pinfunction "3.3V_3.3V") (pintype "bidirectional"))
    )
    (net (code "97") (name "unconnected-(GPSMTK3339-PadVBAT)") (class "Default")
      (node (ref "GPSMTK3339") (pin "VBAT") (pinfunction "VBAT_VBAT") (pintype "bidirectional"))
    )
    (net (code "98") (name "unconnected-(IC1-COMP-Pad4)") (class "Default")
      (node (ref "IC1") (pin "4") (pinfunction "COMP_4") (pintype "bidirectional"))
    )
    (net (code "99") (name "unconnected-(IC1-EP-Pad9)") (class "Default")
      (node (ref "IC1") (pin "9") (pinfunction "EP_9") (pintype "bidirectional"))
    )
    (net (code "100") (name "unconnected-(IC1-SYNCH-Pad2)") (class "Default")
      (node (ref "IC1") (pin "2") (pinfunction "SYNCH_2") (pintype "bidirectional"))
    )
    (net (code "101") (name "unconnected-(IC2-COMP-Pad4)") (class "Default")
      (node (ref "IC2") (pin "4") (pinfunction "COMP_4") (pintype "bidirectional"))
    )
    (net (code "102") (name "unconnected-(IC2-EP-Pad9)") (class "Default")
      (node (ref "IC2") (pin "9") (pinfunction "EP_9") (pintype "bidirectional"))
    )
    (net (code "103") (name "unconnected-(IC2-SYNCH-Pad2)") (class "Default")
      (node (ref "IC2") (pin "2") (pinfunction "SYNCH_2") (pintype "bidirectional"))
    )
    (net (code "104") (name "unconnected-(IC3-COMP-Pad4)") (class "Default")
      (node (ref "IC3") (pin "4") (pinfunction "COMP_4") (pintype "bidirectional"))
    )
    (net (code "105") (name "unconnected-(IC3-EP-Pad9)") (class "Default")
      (node (ref "IC3") (pin "9") (pinfunction "EP_9") (pintype "bidirectional"))
    )
    (net (code "106") (name "unconnected-(IC3-SYNCH-Pad2)") (class "Default")
      (node (ref "IC3") (pin "2") (pinfunction "SYNCH_2") (pintype "bidirectional"))
    )
    (net (code "107") (name "unconnected-(RADIO-G1-Pad10)") (class "Default")
      (node (ref "RADIO") (pin "10") (pinfunction "G1_10") (pintype "bidirectional"))
    )
    (net (code "108") (name "unconnected-(RADIO-G2-Pad11)") (class "Default")
      (node (ref "RADIO") (pin "11") (pinfunction "G2_11") (pintype "bidirectional"))
    )
    (net (code "109") (name "unconnected-(RADIO-G3-Pad12)") (class "Default")
      (node (ref "RADIO") (pin "12") (pinfunction "G3_12") (pintype "bidirectional"))
    )
    (net (code "110") (name "unconnected-(RADIO-G4-Pad13)") (class "Default")
      (node (ref "RADIO") (pin "13") (pinfunction "G4_13") (pintype "bidirectional"))
    )
    (net (code "111") (name "unconnected-(RADIO-G5-Pad14)") (class "Default")
      (node (ref "RADIO") (pin "14") (pinfunction "G5_14") (pintype "bidirectional"))
    )
    (net (code "112") (name "unconnected-(TEENSY4.1-5V-Pad+5V)") (class "Default")
      (node (ref "TEENSY4.1") (pin "+5V") (pinfunction "5V_+5V") (pintype "bidirectional"))
    )
    (net (code "113") (name "unconnected-(TEENSY4.1-Pad3V3-2)") (class "Default")
      (node (ref "TEENSY4.1") (pin "3V3-2") (pinfunction "3V3-2_3V3-2") (pintype "bidirectional"))
    )
    (net (code "114") (name "unconnected-(TEENSY4.1-PadD+)") (class "Default")
      (node (ref "TEENSY4.1") (pin "D+") (pinfunction "D+_D+") (pintype "bidirectional"))
    )
    (net (code "115") (name "unconnected-(TEENSY4.1-PadD-)") (class "Default")
      (node (ref "TEENSY4.1") (pin "D-") (pinfunction "D-_D-") (pintype "bidirectional"))
    )
    (net (code "116") (name "unconnected-(TEENSY4.1-PadDM)") (class "Default")
      (node (ref "TEENSY4.1") (pin "DM") (pinfunction "DM_DM") (pintype "bidirectional"))
    )
    (net (code "117") (name "unconnected-(TEENSY4.1-PadDP)") (class "Default")
      (node (ref "TEENSY4.1") (pin "DP") (pinfunction "DP_DP") (pintype "bidirectional"))
    )
    (net (code "118") (name "unconnected-(TEENSY4.1-PadG)") (class "Default")
      (node (ref "TEENSY4.1") (pin "G") (pinfunction "G_G") (pintype "bidirectional"))
    )
    (net (code "119") (name "unconnected-(TEENSY4.1-PadGND2)") (class "Default")
      (node (ref "TEENSY4.1") (pin "GND2") (pinfunction "GND2_GND2") (pintype "bidirectional"))
    )
    (net (code "120") (name "unconnected-(TEENSY4.1-PadGND4)") (class "Default")
      (node (ref "TEENSY4.1") (pin "GND4") (pinfunction "GND4_GND4") (pintype "bidirectional"))
    )
    (net (code "121") (name "unconnected-(TEENSY4.1-PadGND5)") (class "Default")
      (node (ref "TEENSY4.1") (pin "GND5") (pinfunction "GND5_GND5") (pintype "bidirectional"))
    )
    (net (code "122") (name "unconnected-(TEENSY4.1-PadLED)") (class "Default")
      (node (ref "TEENSY4.1") (pin "LED") (pinfunction "LED_LED") (pintype "bidirectional"))
    )
    (net (code "123") (name "unconnected-(TEENSY4.1-PadON{slash}OFF)") (class "Default")
      (node (ref "TEENSY4.1") (pin "ON/OFF") (pinfunction "ON/OFF_ON/OFF") (pintype "bidirectional"))
    )
    (net (code "124") (name "unconnected-(TEENSY4.1-PadPROGRAM)") (class "Default")
      (node (ref "TEENSY4.1") (pin "PROGRAM") (pinfunction "PROGRAM_PROGRAM") (pintype "bidirectional"))
    )
    (net (code "125") (name "unconnected-(TEENSY4.1-PadR+)") (class "Default")
      (node (ref "TEENSY4.1") (pin "R+") (pinfunction "R+_R+") (pintype "bidirectional"))
    )
    (net (code "126") (name "unconnected-(TEENSY4.1-PadR-)") (class "Default")
      (node (ref "TEENSY4.1") (pin "R-") (pinfunction "R-_R-") (pintype "bidirectional"))
    )
    (net (code "127") (name "unconnected-(TEENSY4.1-PadT+)") (class "Default")
      (node (ref "TEENSY4.1") (pin "T+") (pinfunction "T+_T+") (pintype "bidirectional"))
    )
    (net (code "128") (name "unconnected-(TEENSY4.1-PadT-)") (class "Default")
      (node (ref "TEENSY4.1") (pin "T-") (pinfunction "T-_T-") (pintype "bidirectional"))
    )
    (net (code "129") (name "unconnected-(TEENSY4.1-PadVBAT)") (class "Default")
      (node (ref "TEENSY4.1") (pin "VBAT") (pinfunction "VBAT_VBAT") (pintype "bidirectional"))
    )
    (net (code "130") (name "unconnected-(TEENSY4.1-PadVUSB)") (class "Default")
      (node (ref "TEENSY4.1") (pin "VUSB") (pinfunction "VUSB_VUSB") (pintype "bidirectional"))
    )
  )
)
